# Carolo_schaltplan.net
KiCad netlist of a schematic drawn in EAGLE
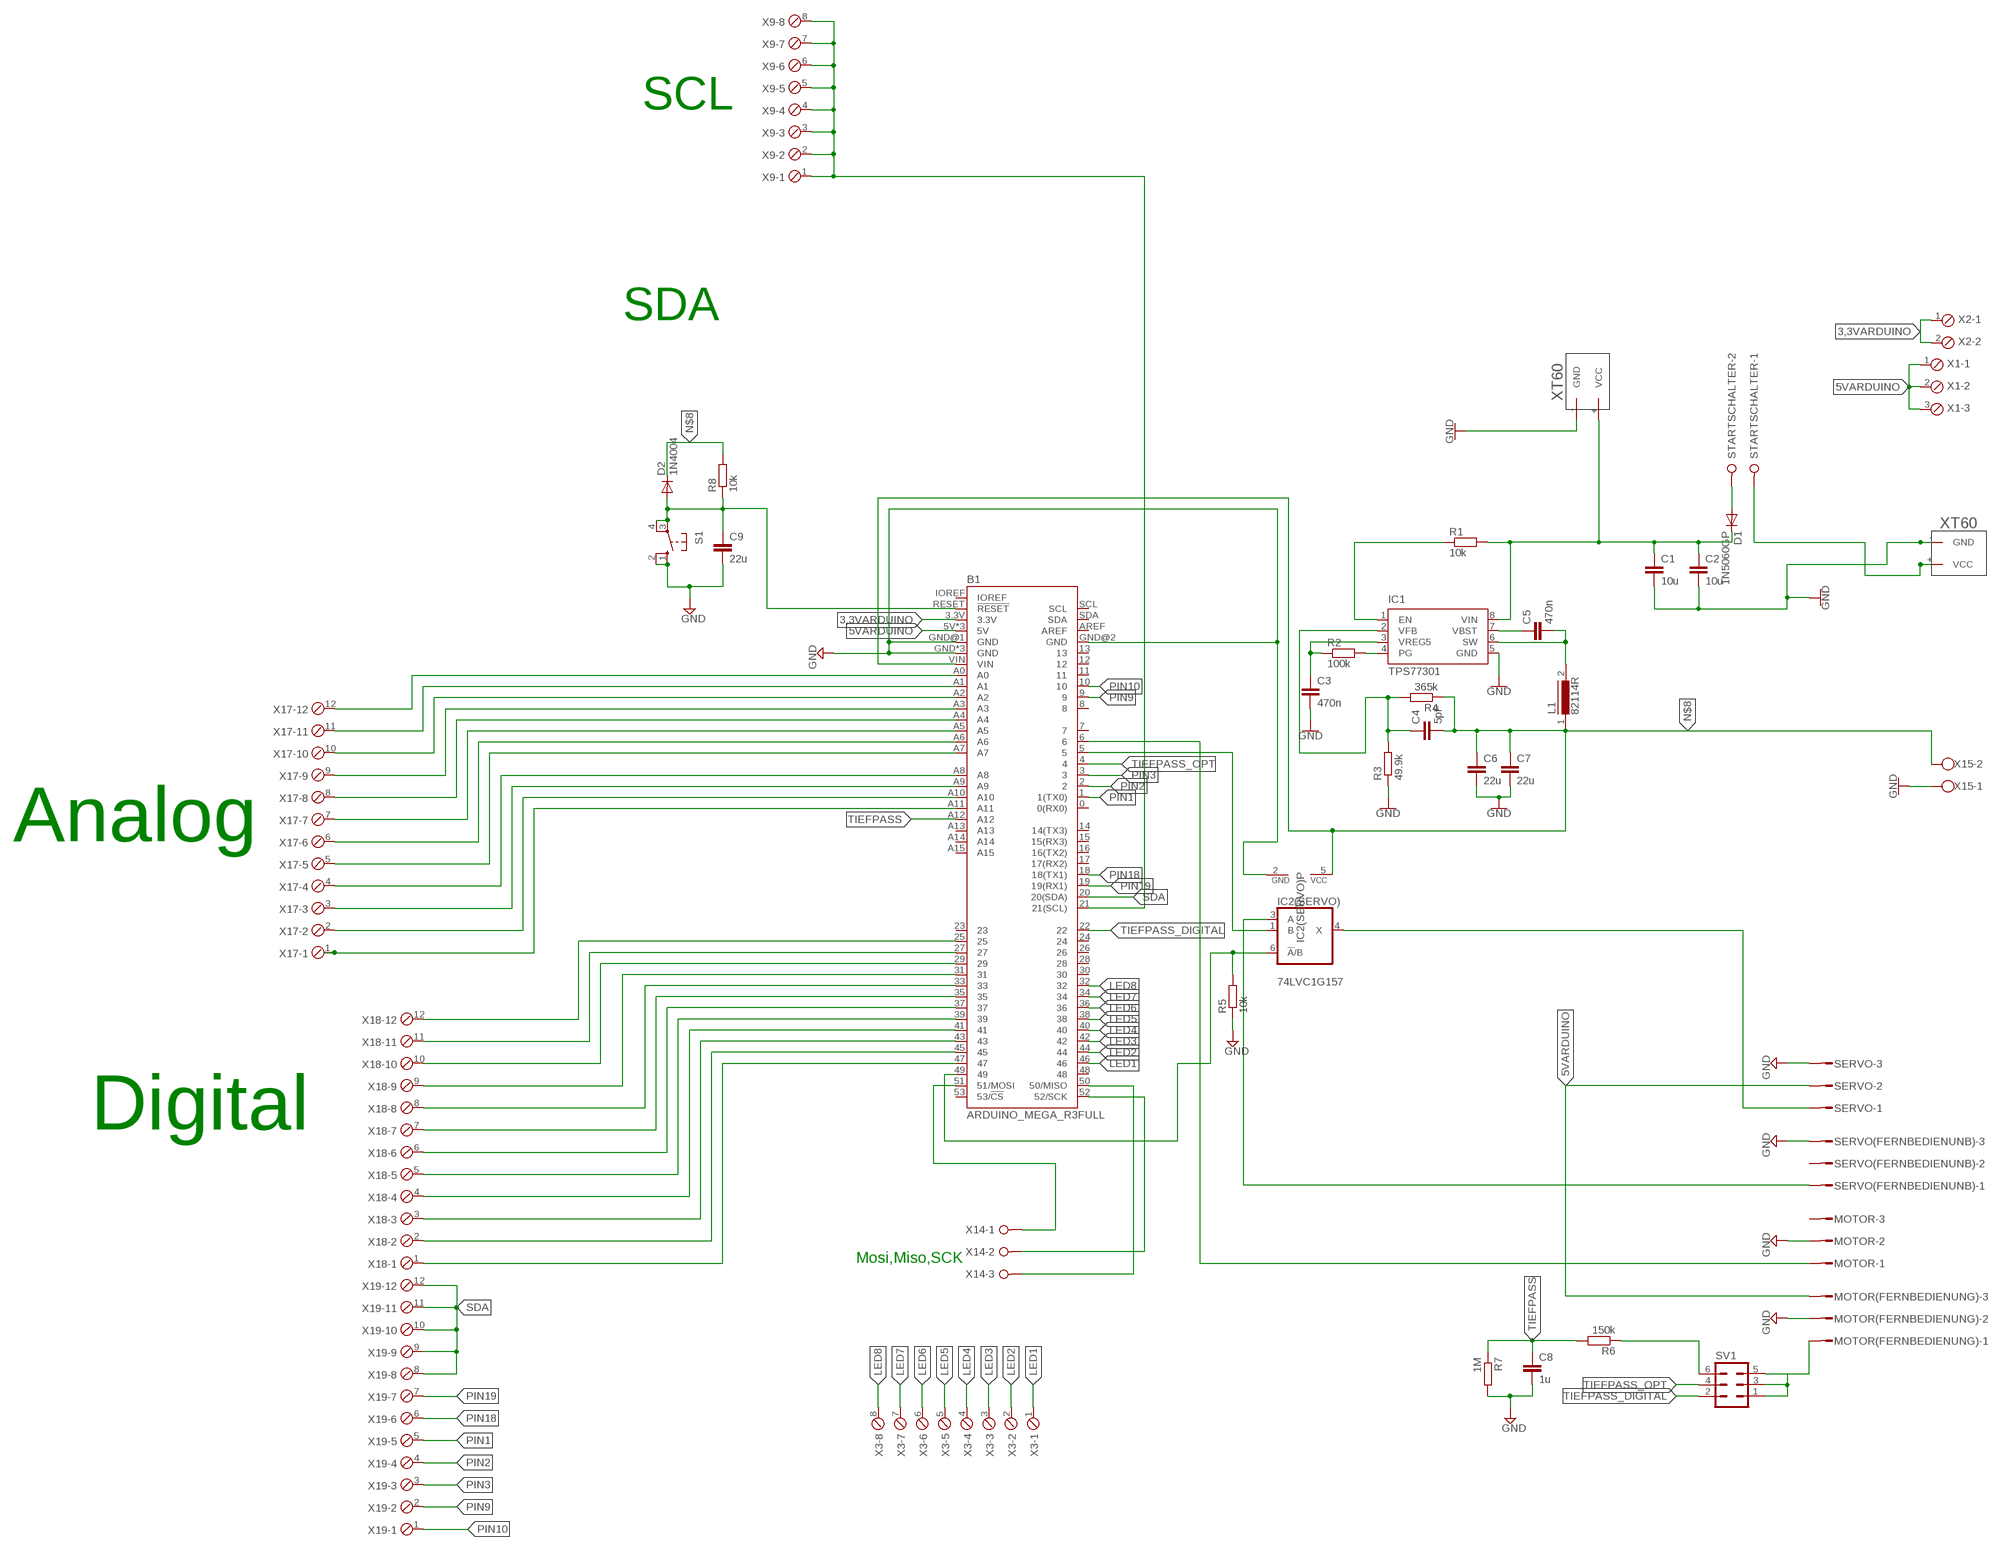
[diagram p0: schematic, sheet 1]

(export (version "E")
  (design (tool "Eeschema 10.0.6"))
  (components
    (comp (ref "B1")
      (value "ARDUINO_MEGA_R3FULL")
      (footprint "eagle-import:ARDUINO_MEGA_NO_SILK")
      (libsource (lib "eagle-import") (part "ARDUINO_MEGA_R3FULL"))
    )
    (comp (ref "C1")
      (value "10u")
      (footprint "eagle-import:C5B2.5")
      (libsource (lib "eagle-import") (part "C5/2.5"))
    )
    (comp (ref "C2")
      (value "10u")
      (footprint "eagle-import:C5B2.5")
      (libsource (lib "eagle-import") (part "C5/2.5"))
    )
    (comp (ref "C3")
      (value "470n")
      (footprint "eagle-import:C5B2.5")
      (libsource (lib "eagle-import") (part "C5/2.5"))
    )
    (comp (ref "C4")
      (value "5pF")
      (footprint "eagle-import:C5B2.5")
      (libsource (lib "eagle-import") (part "C5/2.5"))
    )
    (comp (ref "C5")
      (value "470n")
      (footprint "eagle-import:C5B2.5")
      (libsource (lib "eagle-import") (part "C5/2.5"))
    )
    (comp (ref "C6")
      (value "22u")
      (footprint "eagle-import:C5B2.5")
      (libsource (lib "eagle-import") (part "C5/2.5"))
    )
    (comp (ref "C7")
      (value "22u")
      (footprint "eagle-import:C5B2.5")
      (libsource (lib "eagle-import") (part "C5/2.5"))
    )
    (comp (ref "C8")
      (value "1u")
      (footprint "eagle-import:C5B2.5")
      (libsource (lib "eagle-import") (part "C5/2.5"))
    )
    (comp (ref "C9")
      (value "22u")
      (footprint "eagle-import:C5B2.5")
      (libsource (lib "eagle-import") (part "C5/2.5"))
    )
    (comp (ref "D1")
      (value "1N5060GP")
      (footprint "eagle-import:DO15-12")
      (libsource (lib "eagle-import") (part "1N5060GP"))
    )
    (comp (ref "D2")
      (value "1N4004")
      (footprint "eagle-import:DO41-10")
      (libsource (lib "eagle-import") (part "1N4004"))
    )
    (comp (ref "IC1")
      (value "TPS77301")
      (footprint "eagle-import:SOP-08")
      (fields (field (name "MF") "TEXAS INSTRUMENT CONNECTORS") (field (name "MPN") "TPS77301DGK"))
      (libsource (lib "eagle-import") (part "TPS77301"))
    )
    (comp (ref "IC2(SERVO)")
      (value "74LVC1G157")
      (footprint "eagle-import:DBV_R-PDSO-G6")
      (libsource (lib "eagle-import") (part "741G3157DBVR"))
    )
    (comp (ref "L1")
      (value "82114R")
      (footprint "eagle-import:82114R")
      (libsource (lib "eagle-import") (part "82114R"))
    )
    (comp (ref "MOTOR")
      (value "L03P")
      (footprint "eagle-import:L03P")
      (libsource (lib "eagle-import") (part "L03P"))
    )
    (comp (ref "MOTOR(FERNBEDIENUNG)")
      (value "L03P")
      (footprint "eagle-import:L03P")
      (libsource (lib "eagle-import") (part "L03P"))
    )
    (comp (ref "R1")
      (value "10k")
      (footprint "eagle-import:0309_12")
      (libsource (lib "eagle-import") (part "R-EU_0309/12"))
    )
    (comp (ref "R2")
      (value "100k")
      (footprint "eagle-import:0309_12")
      (libsource (lib "eagle-import") (part "R-EU_0309/12"))
    )
    (comp (ref "R3")
      (value "49.9k")
      (footprint "eagle-import:0309_12")
      (libsource (lib "eagle-import") (part "R-EU_0309/12"))
    )
    (comp (ref "R4")
      (value "365k")
      (footprint "eagle-import:0309_12")
      (libsource (lib "eagle-import") (part "R-EU_0309/12"))
    )
    (comp (ref "R5")
      (value "10k")
      (footprint "eagle-import:0309_12")
      (libsource (lib "eagle-import") (part "R-EU_0309/12"))
    )
    (comp (ref "R6")
      (value "150k")
      (footprint "eagle-import:0309_12")
      (libsource (lib "eagle-import") (part "R-EU_0309/12"))
    )
    (comp (ref "R7")
      (value "1M")
      (footprint "eagle-import:0309_12")
      (libsource (lib "eagle-import") (part "R-EU_0309/12"))
    )
    (comp (ref "R8")
      (value "10k")
      (footprint "eagle-import:0309_12")
      (libsource (lib "eagle-import") (part "R-EU_0309/12"))
    )
    (comp (ref "S1")
      (value "10-XX")
      (footprint "eagle-import:B3F-10XX")
      (fields (field (name "MPN") "B3F-1000"))
      (libsource (lib "eagle-import") (part "10-XX"))
    )
    (comp (ref "SERVO")
      (value "L03P")
      (footprint "eagle-import:L03P")
      (libsource (lib "eagle-import") (part "L03P"))
    )
    (comp (ref "SERVO(FERNBEDIENUNB)")
      (value "L03P")
      (footprint "eagle-import:L03P")
      (libsource (lib "eagle-import") (part "L03P"))
    )
    (comp (ref "STARTSCHALTER")
      (value "W237-02P")
      (footprint "eagle-import:W237-132")
      (libsource (lib "eagle-import") (part "W237-02P"))
    )
    (comp (ref "SV1")
      (value "ML6")
      (footprint "eagle-import:ML6")
      (libsource (lib "eagle-import") (part "ML6"))
    )
    (comp (ref "U$1")
      (value "XT60")
      (footprint "eagle-import:XT60")
      (libsource (lib "eagle-import") (part "XT60"))
    )
    (comp (ref "U$2")
      (value "XT60")
      (footprint "eagle-import:XT60")
      (libsource (lib "eagle-import") (part "XT60"))
    )
    (comp (ref "X1")
      (value "MPT3")
      (footprint "eagle-import:3POL254")
      (libsource (lib "eagle-import") (part "MPT3"))
    )
    (comp (ref "X2")
      (value "MPT2")
      (footprint "eagle-import:2POL254")
      (libsource (lib "eagle-import") (part "MPT2"))
    )
    (comp (ref "X3")
      (value "MPT8")
      (footprint "eagle-import:8POL254")
      (libsource (lib "eagle-import") (part "con-phoenix-254_172_MPT8"))
    )
    (comp (ref "X9")
      (value "MPT8")
      (footprint "eagle-import:8POL254")
      (libsource (lib "eagle-import") (part "MPT8"))
    )
    (comp (ref "X14")
      (value "W237-03P")
      (footprint "eagle-import:W237-133")
      (libsource (lib "eagle-import") (part "W237-03P"))
    )
    (comp (ref "X15")
      (value "W237-102")
      (footprint "eagle-import:W237-102")
      (fields (field (name "MPN") "237-102"))
      (libsource (lib "eagle-import") (part "W237-102"))
    )
    (comp (ref "X17")
      (value "MPT12")
      (footprint "eagle-import:12POL254")
      (libsource (lib "eagle-import") (part "MPT12"))
    )
    (comp (ref "X18")
      (value "MPT12")
      (footprint "eagle-import:12POL254")
      (libsource (lib "eagle-import") (part "MPT12"))
    )
    (comp (ref "X19")
      (value "MPT12")
      (footprint "eagle-import:12POL254")
      (libsource (lib "eagle-import") (part "MPT12"))
    )
  )
  (nets
    (net (code "1") (name "3,3VARDUINO") (class "Default")
      (node (ref "B1") (pin "3.3V") (pinfunction "3.3V_3.3V") (pintype "bidirectional"))
      (node (ref "X2") (pin "1") (pinfunction "1_1") (pintype "passive"))
      (node (ref "X2") (pin "2") (pinfunction "1_2") (pintype "passive"))
    )
    (net (code "2") (name "5VARDUINO") (class "Default")
      (node (ref "B1") (pin "5V") (pinfunction "5V_5V") (pintype "bidirectional"))
      (node (ref "B1") (pin "5V@1") (pinfunction "5V_5V@1") (pintype "bidirectional"))
      (node (ref "B1") (pin "5V@2") (pinfunction "5V_5V@2") (pintype "bidirectional"))
      (node (ref "MOTOR(FERNBEDIENUNG)") (pin "3") (pinfunction "S_3") (pintype "passive"))
      (node (ref "SERVO") (pin "2") (pinfunction "S_2") (pintype "passive"))
      (node (ref "X1") (pin "1") (pinfunction "1_1") (pintype "passive"))
      (node (ref "X1") (pin "2") (pinfunction "1_2") (pintype "passive"))
      (node (ref "X1") (pin "3") (pinfunction "1_3") (pintype "passive"))
    )
    (net (code "3") (name "GND") (class "Default")
      (node (ref "B1") (pin "GND") (pinfunction "GND_GND") (pintype "bidirectional"))
      (node (ref "B1") (pin "GND@1") (pinfunction "GND_GND@1") (pintype "bidirectional"))
      (node (ref "B1") (pin "GND@2") (pinfunction "GND_GND@2") (pintype "bidirectional"))
      (node (ref "B1") (pin "GND@3") (pinfunction "GND_GND@3") (pintype "bidirectional"))
      (node (ref "B1") (pin "GND@4") (pinfunction "GND_GND@4") (pintype "bidirectional"))
      (node (ref "C1") (pin "2") (pinfunction "2_2") (pintype "passive"))
      (node (ref "C2") (pin "2") (pinfunction "2_2") (pintype "passive"))
      (node (ref "C3") (pin "2") (pinfunction "2_2") (pintype "passive"))
      (node (ref "C6") (pin "2") (pinfunction "2_2") (pintype "passive"))
      (node (ref "C7") (pin "2") (pinfunction "2_2") (pintype "passive"))
      (node (ref "C8") (pin "2") (pinfunction "2_2") (pintype "passive"))
      (node (ref "C9") (pin "2") (pinfunction "2_2") (pintype "passive"))
      (node (ref "IC1") (pin "5") (pinfunction "GND_5") (pintype "input"))
      (node (ref "IC2(SERVO)") (pin "2") (pinfunction "GND_2") (pintype "power_in"))
      (node (ref "MOTOR") (pin "2") (pinfunction "S_2") (pintype "passive"))
      (node (ref "MOTOR(FERNBEDIENUNG)") (pin "2") (pinfunction "S_2") (pintype "passive"))
      (node (ref "R3") (pin "1") (pinfunction "1_1") (pintype "passive"))
      (node (ref "R5") (pin "1") (pinfunction "1_1") (pintype "passive"))
      (node (ref "R7") (pin "2") (pinfunction "2_2") (pintype "passive"))
      (node (ref "S1") (pin "1") (pinfunction "S_1") (pintype "passive"))
      (node (ref "S1") (pin "2") (pinfunction "S1_2") (pintype "passive"))
      (node (ref "SERVO") (pin "3") (pinfunction "S_3") (pintype "passive"))
      (node (ref "SERVO(FERNBEDIENUNB)") (pin "3") (pinfunction "S_3") (pintype "passive"))
      (node (ref "U$1") (pin "-") (pinfunction "GND_-") (pintype "bidirectional"))
      (node (ref "U$2") (pin "-") (pinfunction "GND_-") (pintype "bidirectional"))
      (node (ref "X15") (pin "1") (pinfunction "KL_1") (pintype "passive"))
    )
    (net (code "4") (name "LED1") (class "Default")
      (node (ref "B1") (pin "46") (pinfunction "46_46") (pintype "bidirectional"))
      (node (ref "X3") (pin "1") (pinfunction "1_1") (pintype "passive"))
    )
    (net (code "5") (name "LED2") (class "Default")
      (node (ref "B1") (pin "44") (pinfunction "44_44") (pintype "bidirectional"))
      (node (ref "X3") (pin "2") (pinfunction "1_2") (pintype "passive"))
    )
    (net (code "6") (name "LED3") (class "Default")
      (node (ref "B1") (pin "42") (pinfunction "42_42") (pintype "bidirectional"))
      (node (ref "X3") (pin "3") (pinfunction "1_3") (pintype "passive"))
    )
    (net (code "7") (name "LED4") (class "Default")
      (node (ref "B1") (pin "40") (pinfunction "40_40") (pintype "bidirectional"))
      (node (ref "X3") (pin "4") (pinfunction "1_4") (pintype "passive"))
    )
    (net (code "8") (name "LED5") (class "Default")
      (node (ref "B1") (pin "38") (pinfunction "38_38") (pintype "bidirectional"))
      (node (ref "X3") (pin "5") (pinfunction "1_5") (pintype "passive"))
    )
    (net (code "9") (name "LED6") (class "Default")
      (node (ref "B1") (pin "36") (pinfunction "36_36") (pintype "bidirectional"))
      (node (ref "X3") (pin "6") (pinfunction "1_6") (pintype "passive"))
    )
    (net (code "10") (name "LED7") (class "Default")
      (node (ref "B1") (pin "34") (pinfunction "34_34") (pintype "bidirectional"))
      (node (ref "X3") (pin "7") (pinfunction "1_7") (pintype "passive"))
    )
    (net (code "11") (name "LED8") (class "Default")
      (node (ref "B1") (pin "32") (pinfunction "32_32") (pintype "bidirectional"))
      (node (ref "X3") (pin "8") (pinfunction "1_8") (pintype "passive"))
    )
    (net (code "12") (name "N$8") (class "Default")
      (node (ref "B1") (pin "VIN") (pinfunction "VIN_VIN") (pintype "bidirectional"))
      (node (ref "C4") (pin "2") (pinfunction "2_2") (pintype "passive"))
      (node (ref "C6") (pin "1") (pinfunction "1_1") (pintype "passive"))
      (node (ref "C7") (pin "1") (pinfunction "1_1") (pintype "passive"))
      (node (ref "D2") (pin "C") (pinfunction "C_C") (pintype "passive"))
      (node (ref "IC2(SERVO)") (pin "5") (pinfunction "VCC_5") (pintype "power_in"))
      (node (ref "L1") (pin "1") (pinfunction "1_1") (pintype "passive"))
      (node (ref "R4") (pin "1") (pinfunction "1_1") (pintype "passive"))
      (node (ref "R8") (pin "2") (pinfunction "2_2") (pintype "passive"))
      (node (ref "X15") (pin "2") (pinfunction "KL_2") (pintype "passive"))
    )
    (net (code "13") (name "Net-(B1-21(SCL))") (class "Default")
      (node (ref "B1") (pin "21") (pinfunction "21(SCL)_21") (pintype "bidirectional"))
      (node (ref "X9") (pin "1") (pinfunction "1_1") (pintype "passive"))
      (node (ref "X9") (pin "2") (pinfunction "1_2") (pintype "passive"))
      (node (ref "X9") (pin "3") (pinfunction "1_3") (pintype "passive"))
      (node (ref "X9") (pin "4") (pinfunction "1_4") (pintype "passive"))
      (node (ref "X9") (pin "5") (pinfunction "1_5") (pintype "passive"))
      (node (ref "X9") (pin "6") (pinfunction "1_6") (pintype "passive"))
      (node (ref "X9") (pin "7") (pinfunction "1_7") (pintype "passive"))
      (node (ref "X9") (pin "8") (pinfunction "1_8") (pintype "passive"))
    )
    (net (code "14") (name "Net-(B1-50{slash}MISO)") (class "Default")
      (node (ref "B1") (pin "50") (pinfunction "50/MISO_50") (pintype "bidirectional"))
      (node (ref "X14") (pin "3") (pinfunction "KL_3") (pintype "passive"))
    )
    (net (code "15") (name "Net-(B1-51{slash}MOSI)") (class "Default")
      (node (ref "B1") (pin "51") (pinfunction "51/MOSI_51") (pintype "bidirectional"))
      (node (ref "X14") (pin "1") (pinfunction "KL_1") (pintype "passive"))
    )
    (net (code "16") (name "Net-(B1-52{slash}SCK)") (class "Default")
      (node (ref "B1") (pin "52") (pinfunction "52/SCK_52") (pintype "bidirectional"))
      (node (ref "X14") (pin "2") (pinfunction "KL_2") (pintype "passive"))
    )
    (net (code "17") (name "Net-(B1-Pad47)") (class "Default")
      (node (ref "B1") (pin "47") (pinfunction "47_47") (pintype "bidirectional"))
      (node (ref "X18") (pin "1") (pinfunction "1_1") (pintype "passive"))
    )
    (net (code "18") (name "Net-(B1-PadA11)") (class "Default")
      (node (ref "B1") (pin "A11") (pinfunction "A11_A11") (pintype "bidirectional"))
      (node (ref "X17") (pin "1") (pinfunction "1_1") (pintype "passive"))
    )
    (net (code "19") (name "Net-(B1-~{RESET})") (class "Default")
      (node (ref "B1") (pin "RESET") (pinfunction "~{RESET}_RESET") (pintype "bidirectional"))
      (node (ref "C9") (pin "1") (pinfunction "1_1") (pintype "passive"))
      (node (ref "D2") (pin "A") (pinfunction "A_A") (pintype "passive"))
      (node (ref "R8") (pin "1") (pinfunction "1_1") (pintype "passive"))
      (node (ref "S1") (pin "3") (pinfunction "P_3") (pintype "passive"))
      (node (ref "S1") (pin "4") (pinfunction "P1_4") (pintype "passive"))
    )
    (net (code "20") (name "Net-(IC1-EN)") (class "Default")
      (node (ref "IC1") (pin "1") (pinfunction "EN_1") (pintype "input"))
      (node (ref "R1") (pin "1") (pinfunction "1_1") (pintype "passive"))
    )
    (net (code "21") (name "Net-(IC1-PG)") (class "Default")
      (node (ref "IC1") (pin "4") (pinfunction "PG_4") (pintype "power_in"))
      (node (ref "R2") (pin "2") (pinfunction "2_2") (pintype "passive"))
    )
    (net (code "22") (name "Net-(IC1-SW)") (class "Default")
      (node (ref "C5") (pin "2") (pinfunction "2_2") (pintype "passive"))
      (node (ref "IC1") (pin "6") (pinfunction "SW_6") (pintype "input"))
      (node (ref "L1") (pin "2") (pinfunction "2_2") (pintype "passive"))
    )
    (net (code "23") (name "Net-(IC1-VBST)") (class "Default")
      (node (ref "C5") (pin "1") (pinfunction "1_1") (pintype "passive"))
      (node (ref "IC1") (pin "7") (pinfunction "VBST_7") (pintype "output"))
    )
    (net (code "24") (name "Net-(IC1-VFB)") (class "Default")
      (node (ref "C4") (pin "1") (pinfunction "1_1") (pintype "passive"))
      (node (ref "IC1") (pin "2") (pinfunction "VFB_2") (pintype "input"))
      (node (ref "R3") (pin "2") (pinfunction "2_2") (pintype "passive"))
      (node (ref "R4") (pin "2") (pinfunction "2_2") (pintype "passive"))
    )
    (net (code "25") (name "Net-(IC1-VIN)") (class "Default")
      (node (ref "C1") (pin "1") (pinfunction "1_1") (pintype "passive"))
      (node (ref "C2") (pin "1") (pinfunction "1_1") (pintype "passive"))
      (node (ref "D1") (pin "C") (pinfunction "C_C") (pintype "passive"))
      (node (ref "IC1") (pin "8") (pinfunction "VIN_8") (pintype "passive"))
      (node (ref "R1") (pin "2") (pinfunction "2_2") (pintype "passive"))
      (node (ref "U$2") (pin "+") (pinfunction "VCC_+") (pintype "bidirectional"))
    )
    (net (code "26") (name "Net-(IC1-VREG5)") (class "Default")
      (node (ref "C3") (pin "1") (pinfunction "1_1") (pintype "passive"))
      (node (ref "IC1") (pin "3") (pinfunction "VREG5_3") (pintype "input"))
      (node (ref "R2") (pin "1") (pinfunction "1_1") (pintype "passive"))
    )
    (net (code "27") (name "Net-(IC2(SERVO)A-A)") (class "Default")
      (node (ref "IC2(SERVO)") (pin "3") (pinfunction "A_3") (pintype "bidirectional"))
      (node (ref "SERVO(FERNBEDIENUNB)") (pin "1") (pinfunction "S_1") (pintype "passive"))
    )
    (net (code "28") (name "Net-(IC2(SERVO)A-B)") (class "Default")
      (node (ref "B1") (pin "5") (pinfunction "5_5") (pintype "bidirectional"))
      (node (ref "IC2(SERVO)") (pin "1") (pinfunction "B_1") (pintype "bidirectional"))
    )
    (net (code "29") (name "Net-(IC2(SERVO)A-X)") (class "Default")
      (node (ref "IC2(SERVO)") (pin "4") (pinfunction "X_4") (pintype "bidirectional"))
      (node (ref "SERVO") (pin "1") (pinfunction "S_1") (pintype "passive"))
    )
    (net (code "30") (name "Net-(IC2(SERVO)A-~{A}{slash}B)") (class "Default")
      (node (ref "B1") (pin "49") (pinfunction "49_49") (pintype "bidirectional"))
      (node (ref "IC2(SERVO)") (pin "6") (pinfunction "~{A}/B_6") (pintype "input"))
      (node (ref "R5") (pin "2") (pinfunction "2_2") (pintype "passive"))
    )
    (net (code "31") (name "Net-(MOTOR(FERNBEDIENUNG)A-S)") (class "Default")
      (node (ref "MOTOR(FERNBEDIENUNG)") (pin "1") (pinfunction "S_1") (pintype "passive"))
      (node (ref "SV1") (pin "1") (pinfunction "1_1") (pintype "passive"))
      (node (ref "SV1") (pin "3") (pinfunction "3_3") (pintype "passive"))
      (node (ref "SV1") (pin "5") (pinfunction "5_5") (pintype "passive"))
    )
    (net (code "32") (name "Net-(MOTORA-S)") (class "Default")
      (node (ref "B1") (pin "6") (pinfunction "6_6") (pintype "bidirectional"))
      (node (ref "MOTOR") (pin "1") (pinfunction "S_1") (pintype "passive"))
    )
    (net (code "33") (name "Net-(R6-Pad1)") (class "Default")
      (node (ref "R6") (pin "1") (pinfunction "1_1") (pintype "passive"))
      (node (ref "SV1") (pin "6") (pinfunction "6_6") (pintype "passive"))
    )
    (net (code "34") (name "Net-(STARTSCHALTERA-KL)") (class "Default")
      (node (ref "STARTSCHALTER") (pin "1") (pinfunction "KL_1") (pintype "passive"))
      (node (ref "U$1") (pin "+") (pinfunction "VCC_+") (pintype "bidirectional"))
    )
    (net (code "35") (name "Net-(STARTSCHALTERB-KL)") (class "Default")
      (node (ref "D1") (pin "A") (pinfunction "A_A") (pintype "passive"))
      (node (ref "STARTSCHALTER") (pin "2") (pinfunction "KL_2") (pintype "passive"))
    )
    (net (code "36") (name "Net-(X17B-1)") (class "Default")
      (node (ref "B1") (pin "A2") (pinfunction "A2_A2") (pintype "bidirectional"))
      (node (ref "X17") (pin "10") (pinfunction "1_10") (pintype "passive"))
    )
    (net (code "37") (name "Net-(X17C-1)") (class "Default")
      (node (ref "B1") (pin "A1") (pinfunction "A1_A1") (pintype "bidirectional"))
      (node (ref "X17") (pin "11") (pinfunction "1_11") (pintype "passive"))
    )
    (net (code "38") (name "Net-(X17D-1)") (class "Default")
      (node (ref "B1") (pin "A0") (pinfunction "A0_A0") (pintype "bidirectional"))
      (node (ref "X17") (pin "12") (pinfunction "1_12") (pintype "passive"))
    )
    (net (code "39") (name "Net-(X17E-1)") (class "Default")
      (node (ref "B1") (pin "A10") (pinfunction "A10_A10") (pintype "bidirectional"))
      (node (ref "X17") (pin "2") (pinfunction "1_2") (pintype "passive"))
    )
    (net (code "40") (name "Net-(X17F-1)") (class "Default")
      (node (ref "B1") (pin "A9") (pinfunction "A9_A9") (pintype "bidirectional"))
      (node (ref "X17") (pin "3") (pinfunction "1_3") (pintype "passive"))
    )
    (net (code "41") (name "Net-(X17G-1)") (class "Default")
      (node (ref "B1") (pin "A8") (pinfunction "A8_A8") (pintype "bidirectional"))
      (node (ref "X17") (pin "4") (pinfunction "1_4") (pintype "passive"))
    )
    (net (code "42") (name "Net-(X17H-1)") (class "Default")
      (node (ref "B1") (pin "A7") (pinfunction "A7_A7") (pintype "bidirectional"))
      (node (ref "X17") (pin "5") (pinfunction "1_5") (pintype "passive"))
    )
    (net (code "43") (name "Net-(X17I-1)") (class "Default")
      (node (ref "B1") (pin "A6") (pinfunction "A6_A6") (pintype "bidirectional"))
      (node (ref "X17") (pin "6") (pinfunction "1_6") (pintype "passive"))
    )
    (net (code "44") (name "Net-(X17J-1)") (class "Default")
      (node (ref "B1") (pin "A5") (pinfunction "A5_A5") (pintype "bidirectional"))
      (node (ref "X17") (pin "7") (pinfunction "1_7") (pintype "passive"))
    )
    (net (code "45") (name "Net-(X17K-1)") (class "Default")
      (node (ref "B1") (pin "A4") (pinfunction "A4_A4") (pintype "bidirectional"))
      (node (ref "X17") (pin "8") (pinfunction "1_8") (pintype "passive"))
    )
    (net (code "46") (name "Net-(X17L-1)") (class "Default")
      (node (ref "B1") (pin "A3") (pinfunction "A3_A3") (pintype "bidirectional"))
      (node (ref "X17") (pin "9") (pinfunction "1_9") (pintype "passive"))
    )
    (net (code "47") (name "Net-(X18B-1)") (class "Default")
      (node (ref "B1") (pin "29") (pinfunction "29_29") (pintype "bidirectional"))
      (node (ref "X18") (pin "10") (pinfunction "1_10") (pintype "passive"))
    )
    (net (code "48") (name "Net-(X18C-1)") (class "Default")
      (node (ref "B1") (pin "27") (pinfunction "27_27") (pintype "bidirectional"))
      (node (ref "X18") (pin "11") (pinfunction "1_11") (pintype "passive"))
    )
    (net (code "49") (name "Net-(X18D-1)") (class "Default")
      (node (ref "B1") (pin "25") (pinfunction "25_25") (pintype "bidirectional"))
      (node (ref "X18") (pin "12") (pinfunction "1_12") (pintype "passive"))
    )
    (net (code "50") (name "Net-(X18E-1)") (class "Default")
      (node (ref "B1") (pin "45") (pinfunction "45_45") (pintype "bidirectional"))
      (node (ref "X18") (pin "2") (pinfunction "1_2") (pintype "passive"))
    )
    (net (code "51") (name "Net-(X18F-1)") (class "Default")
      (node (ref "B1") (pin "43") (pinfunction "43_43") (pintype "bidirectional"))
      (node (ref "X18") (pin "3") (pinfunction "1_3") (pintype "passive"))
    )
    (net (code "52") (name "Net-(X18G-1)") (class "Default")
      (node (ref "B1") (pin "41") (pinfunction "41_41") (pintype "bidirectional"))
      (node (ref "X18") (pin "4") (pinfunction "1_4") (pintype "passive"))
    )
    (net (code "53") (name "Net-(X18H-1)") (class "Default")
      (node (ref "B1") (pin "39") (pinfunction "39_39") (pintype "bidirectional"))
      (node (ref "X18") (pin "5") (pinfunction "1_5") (pintype "passive"))
    )
    (net (code "54") (name "Net-(X18I-1)") (class "Default")
      (node (ref "B1") (pin "37") (pinfunction "37_37") (pintype "bidirectional"))
      (node (ref "X18") (pin "6") (pinfunction "1_6") (pintype "passive"))
    )
    (net (code "55") (name "Net-(X18J-1)") (class "Default")
      (node (ref "B1") (pin "35") (pinfunction "35_35") (pintype "bidirectional"))
      (node (ref "X18") (pin "7") (pinfunction "1_7") (pintype "passive"))
    )
    (net (code "56") (name "Net-(X18K-1)") (class "Default")
      (node (ref "B1") (pin "33") (pinfunction "33_33") (pintype "bidirectional"))
      (node (ref "X18") (pin "8") (pinfunction "1_8") (pintype "passive"))
    )
    (net (code "57") (name "Net-(X18L-1)") (class "Default")
      (node (ref "B1") (pin "31") (pinfunction "31_31") (pintype "bidirectional"))
      (node (ref "X18") (pin "9") (pinfunction "1_9") (pintype "passive"))
    )
    (net (code "58") (name "PIN1") (class "Default")
      (node (ref "B1") (pin "1") (pinfunction "1(TX0)_1") (pintype "bidirectional"))
      (node (ref "X19") (pin "5") (pinfunction "1_5") (pintype "passive"))
    )
    (net (code "59") (name "PIN2") (class "Default")
      (node (ref "B1") (pin "2") (pinfunction "2_2") (pintype "bidirectional"))
      (node (ref "X19") (pin "4") (pinfunction "1_4") (pintype "passive"))
    )
    (net (code "60") (name "PIN3") (class "Default")
      (node (ref "B1") (pin "3") (pinfunction "3_3") (pintype "bidirectional"))
      (node (ref "X19") (pin "3") (pinfunction "1_3") (pintype "passive"))
    )
    (net (code "61") (name "PIN9") (class "Default")
      (node (ref "B1") (pin "9") (pinfunction "9_9") (pintype "bidirectional"))
      (node (ref "X19") (pin "2") (pinfunction "1_2") (pintype "passive"))
    )
    (net (code "62") (name "PIN10") (class "Default")
      (node (ref "B1") (pin "10") (pinfunction "10_10") (pintype "bidirectional"))
      (node (ref "X19") (pin "1") (pinfunction "1_1") (pintype "passive"))
    )
    (net (code "63") (name "PIN18") (class "Default")
      (node (ref "B1") (pin "18") (pinfunction "18(TX1)_18") (pintype "bidirectional"))
      (node (ref "X19") (pin "6") (pinfunction "1_6") (pintype "passive"))
    )
    (net (code "64") (name "PIN19") (class "Default")
      (node (ref "B1") (pin "19") (pinfunction "19(RX1)_19") (pintype "bidirectional"))
      (node (ref "X19") (pin "7") (pinfunction "1_7") (pintype "passive"))
    )
    (net (code "65") (name "SDA") (class "Default")
      (node (ref "B1") (pin "20") (pinfunction "20(SDA)_20") (pintype "bidirectional"))
      (node (ref "X19") (pin "10") (pinfunction "1_10") (pintype "passive"))
      (node (ref "X19") (pin "11") (pinfunction "1_11") (pintype "passive"))
      (node (ref "X19") (pin "12") (pinfunction "1_12") (pintype "passive"))
      (node (ref "X19") (pin "8") (pinfunction "1_8") (pintype "passive"))
      (node (ref "X19") (pin "9") (pinfunction "1_9") (pintype "passive"))
    )
    (net (code "66") (name "TIEFPASS") (class "Default")
      (node (ref "B1") (pin "A12") (pinfunction "A12_A12") (pintype "bidirectional"))
      (node (ref "C8") (pin "1") (pinfunction "1_1") (pintype "passive"))
      (node (ref "R6") (pin "2") (pinfunction "2_2") (pintype "passive"))
      (node (ref "R7") (pin "1") (pinfunction "1_1") (pintype "passive"))
    )
    (net (code "67") (name "TIEFPASS_DIGITAL") (class "Default")
      (node (ref "B1") (pin "22") (pinfunction "22_22") (pintype "bidirectional"))
      (node (ref "SV1") (pin "2") (pinfunction "2_2") (pintype "passive"))
    )
    (net (code "68") (name "TIEFPASS_OPT") (class "Default")
      (node (ref "B1") (pin "4") (pinfunction "4_4") (pintype "bidirectional"))
      (node (ref "SV1") (pin "4") (pinfunction "4_4") (pintype "passive"))
    )
    (net (code "69") (name "unconnected-(B1-0(RX0)-Pad0)") (class "Default")
      (node (ref "B1") (pin "0") (pinfunction "0(RX0)_0") (pintype "bidirectional"))
    )
    (net (code "70") (name "unconnected-(B1-14(TX3)-Pad14)") (class "Default")
      (node (ref "B1") (pin "14") (pinfunction "14(TX3)_14") (pintype "bidirectional"))
    )
    (net (code "71") (name "unconnected-(B1-15(RX3)-Pad15)") (class "Default")
      (node (ref "B1") (pin "15") (pinfunction "15(RX3)_15") (pintype "bidirectional"))
    )
    (net (code "72") (name "unconnected-(B1-16(TX2)-Pad16)") (class "Default")
      (node (ref "B1") (pin "16") (pinfunction "16(TX2)_16") (pintype "bidirectional"))
    )
    (net (code "73") (name "unconnected-(B1-17(RX2)-Pad17)") (class "Default")
      (node (ref "B1") (pin "17") (pinfunction "17(RX2)_17") (pintype "bidirectional"))
    )
    (net (code "74") (name "unconnected-(B1-53{slash}~{CS}-Pad53)") (class "Default")
      (node (ref "B1") (pin "53") (pinfunction "53/~{CS}_53") (pintype "bidirectional"))
    )
    (net (code "75") (name "unconnected-(B1-Pad7)") (class "Default")
      (node (ref "B1") (pin "7") (pinfunction "7_7") (pintype "bidirectional"))
    )
    (net (code "76") (name "unconnected-(B1-Pad8)") (class "Default")
      (node (ref "B1") (pin "8") (pinfunction "8_8") (pintype "bidirectional"))
    )
    (net (code "77") (name "unconnected-(B1-Pad11)") (class "Default")
      (node (ref "B1") (pin "11") (pinfunction "11_11") (pintype "bidirectional"))
    )
    (net (code "78") (name "unconnected-(B1-Pad12)") (class "Default")
      (node (ref "B1") (pin "12") (pinfunction "12_12") (pintype "bidirectional"))
    )
    (net (code "79") (name "unconnected-(B1-Pad13)") (class "Default")
      (node (ref "B1") (pin "13") (pinfunction "13_13") (pintype "bidirectional"))
    )
    (net (code "80") (name "unconnected-(B1-Pad23)") (class "Default")
      (node (ref "B1") (pin "23") (pinfunction "23_23") (pintype "bidirectional"))
    )
    (net (code "81") (name "unconnected-(B1-Pad24)") (class "Default")
      (node (ref "B1") (pin "24") (pinfunction "24_24") (pintype "bidirectional"))
    )
    (net (code "82") (name "unconnected-(B1-Pad26)") (class "Default")
      (node (ref "B1") (pin "26") (pinfunction "26_26") (pintype "bidirectional"))
    )
    (net (code "83") (name "unconnected-(B1-Pad28)") (class "Default")
      (node (ref "B1") (pin "28") (pinfunction "28_28") (pintype "bidirectional"))
    )
    (net (code "84") (name "unconnected-(B1-Pad30)") (class "Default")
      (node (ref "B1") (pin "30") (pinfunction "30_30") (pintype "bidirectional"))
    )
    (net (code "85") (name "unconnected-(B1-Pad48)") (class "Default")
      (node (ref "B1") (pin "48") (pinfunction "48_48") (pintype "bidirectional"))
    )
    (net (code "86") (name "unconnected-(B1-PadA13)") (class "Default")
      (node (ref "B1") (pin "A13") (pinfunction "A13_A13") (pintype "bidirectional"))
    )
    (net (code "87") (name "unconnected-(B1-PadA14)") (class "Default")
      (node (ref "B1") (pin "A14") (pinfunction "A14_A14") (pintype "bidirectional"))
    )
    (net (code "88") (name "unconnected-(B1-PadA15)") (class "Default")
      (node (ref "B1") (pin "A15") (pinfunction "A15_A15") (pintype "bidirectional"))
    )
    (net (code "89") (name "unconnected-(B1-PadAREF)") (class "Default")
      (node (ref "B1") (pin "AREF") (pinfunction "AREF_AREF") (pintype "bidirectional"))
    )
    (net (code "90") (name "unconnected-(B1-PadIOREF)") (class "Default")
      (node (ref "B1") (pin "IOREF") (pinfunction "IOREF_IOREF") (pintype "bidirectional"))
    )
    (net (code "91") (name "unconnected-(B1-PadSCL)") (class "Default")
      (node (ref "B1") (pin "SCL") (pinfunction "SCL_SCL") (pintype "bidirectional"))
    )
    (net (code "92") (name "unconnected-(B1-PadSDA)") (class "Default")
      (node (ref "B1") (pin "SDA") (pinfunction "SDA_SDA") (pintype "bidirectional"))
    )
    (net (code "93") (name "unconnected-(MOTORC-S-Pad3)") (class "Default")
      (node (ref "MOTOR") (pin "3") (pinfunction "S_3") (pintype "passive"))
    )
    (net (code "94") (name "unconnected-(SERVO(FERNBEDIENUNB)B-S-Pad2)") (class "Default")
      (node (ref "SERVO(FERNBEDIENUNB)") (pin "2") (pinfunction "S_2") (pintype "passive"))
    )
  )
)
